# Shield.net
KiCad netlist of a schematic drawn in EAGLE
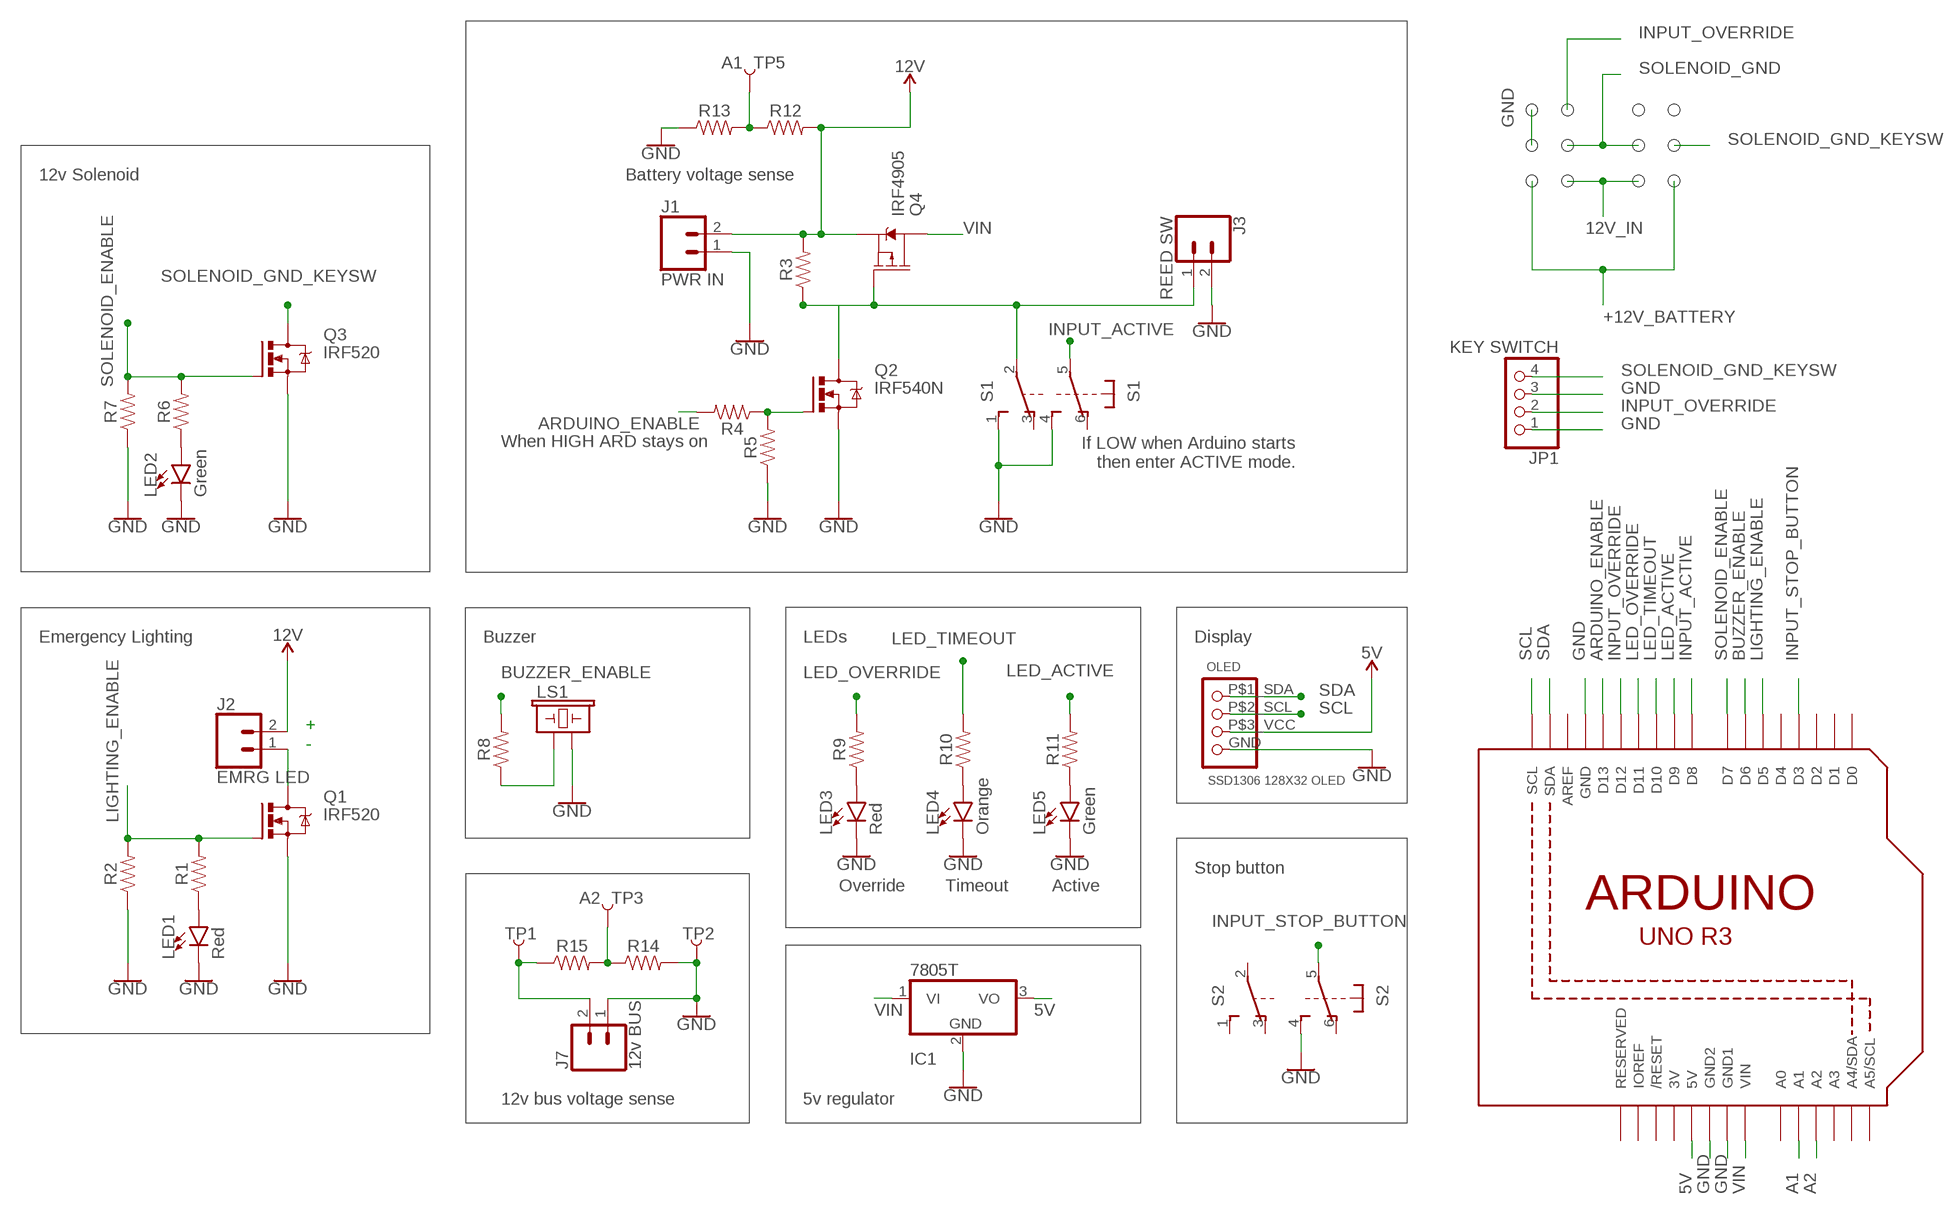
[diagram p0: schematic, sheet 1]

(export (version "E")
  (design (tool "Eeschema 10.0.6"))
  (components
    (comp (ref "IC1")
      (value "7805T")
      (footprint "eagle-import:TO220H")
      (libsource (lib "eagle-import") (part "78T05"))
    )
    (comp (ref "J1")
      (value "PWR IN")
      (footprint "eagle-import:SCREWTERMINAL-5MM-2")
      (libsource (lib "eagle-import") (part "CONN_025MM"))
    )
    (comp (ref "J2")
      (value "EMRG LED")
      (footprint "eagle-import:SCREWTERMINAL-5MM-2")
      (libsource (lib "eagle-import") (part "CONN_025MM"))
    )
    (comp (ref "J3")
      (value "REED SW")
      (footprint "eagle-import:SCREWTERMINAL-5MM-2")
      (libsource (lib "eagle-import") (part "CONN_025MM"))
    )
    (comp (ref "J7")
      (value "12v BUS")
      (footprint "eagle-import:SCREWTERMINAL-5MM-2")
      (libsource (lib "eagle-import") (part "CONN_025MM"))
    )
    (comp (ref "JP1")
      (value "KEY SWITCH")
      (footprint "eagle-import:1X04")
      (libsource (lib "eagle-import") (part "PINHD-1X4"))
    )
    (comp (ref "LED1")
      (value "Red")
      (footprint "eagle-import:LED_3MM")
      (libsource (lib "eagle-import") (part "LED3MM"))
    )
    (comp (ref "LED2")
      (value "Green")
      (footprint "eagle-import:LED_3MM")
      (libsource (lib "eagle-import") (part "LED3MM"))
    )
    (comp (ref "LED3")
      (value "Red")
      (footprint "eagle-import:LED_3MM")
      (libsource (lib "eagle-import") (part "LED3MM"))
    )
    (comp (ref "LED4")
      (value "Orange")
      (footprint "eagle-import:LED_3MM")
      (libsource (lib "eagle-import") (part "LED3MM"))
    )
    (comp (ref "LED5")
      (value "Green")
      (footprint "eagle-import:LED_3MM")
      (libsource (lib "eagle-import") (part "LED3MM"))
    )
    (comp (ref "LS1")
      (value "BUZZER")
      (footprint "eagle-import:BUZZER-12MM-KIT")
      (libsource (lib "eagle-import") (part "BUZZER-PTH_KIT"))
    )
    (comp (ref "OLED")
      (value "SSD1306 128X32 OLED")
      (footprint "eagle-import:SSD1306_128X32_OLED")
      (libsource (lib "eagle-import") (part "SSD1306_128X32_OLED"))
    )
    (comp (ref "Q1")
      (value "IRF520")
      (footprint "eagle-import:TO220BV")
      (libsource (lib "eagle-import") (part "IRF520"))
    )
    (comp (ref "Q2")
      (value "IRF540N")
      (footprint "eagle-import:TO220BV")
      (libsource (lib "eagle-import") (part "IRF540"))
    )
    (comp (ref "Q3")
      (value "IRF520")
      (footprint "eagle-import:TO220BV")
      (libsource (lib "eagle-import") (part "IRF520"))
    )
    (comp (ref "Q4")
      (value "IRF4905")
      (footprint "eagle-import:TO220V")
      (libsource (lib "eagle-import") (part "MOSFET_PCH-NDP6020P"))
    )
    (comp (ref "R1")
      (value "1k")
      (footprint "eagle-import:AXIAL-0.3")
      (libsource (lib "eagle-import") (part "1KOHM-HORIZ-1/4W-5%"))
    )
    (comp (ref "R2")
      (value "1k")
      (footprint "eagle-import:AXIAL-0.3")
      (libsource (lib "eagle-import") (part "1KOHM-HORIZ-1/4W-5%"))
    )
    (comp (ref "R3")
      (value "100k")
      (footprint "eagle-import:AXIAL-0.3")
      (libsource (lib "eagle-import") (part "1KOHM-HORIZ-1/4W-5%"))
    )
    (comp (ref "R4")
      (value "100")
      (footprint "eagle-import:AXIAL-0.3")
      (libsource (lib "eagle-import") (part "1KOHM-HORIZ-1/4W-5%"))
    )
    (comp (ref "R5")
      (value "10k")
      (footprint "eagle-import:AXIAL-0.3")
      (libsource (lib "eagle-import") (part "1KOHM-HORIZ-1/4W-5%"))
    )
    (comp (ref "R6")
      (value "1k")
      (footprint "eagle-import:AXIAL-0.3")
      (libsource (lib "eagle-import") (part "1KOHM-HORIZ-1/4W-5%"))
    )
    (comp (ref "R7")
      (value "1k")
      (footprint "eagle-import:AXIAL-0.3")
      (libsource (lib "eagle-import") (part "1KOHM-HORIZ-1/4W-5%"))
    )
    (comp (ref "R8")
      (value "100")
      (footprint "eagle-import:AXIAL-0.3")
      (libsource (lib "eagle-import") (part "1KOHM-HORIZ-1/4W-5%"))
    )
    (comp (ref "R9")
      (value "330")
      (footprint "eagle-import:AXIAL-0.3")
      (libsource (lib "eagle-import") (part "1KOHM-HORIZ-1/4W-5%"))
    )
    (comp (ref "R10")
      (value "330")
      (footprint "eagle-import:AXIAL-0.3")
      (libsource (lib "eagle-import") (part "1KOHM-HORIZ-1/4W-5%"))
    )
    (comp (ref "R11")
      (value "330")
      (footprint "eagle-import:AXIAL-0.3")
      (libsource (lib "eagle-import") (part "1KOHM-HORIZ-1/4W-5%"))
    )
    (comp (ref "R12")
      (value "1m")
      (footprint "eagle-import:AXIAL-0.3")
      (libsource (lib "eagle-import") (part "1KOHM-HORIZ-1/4W-5%"))
    )
    (comp (ref "R13")
      (value "100k")
      (footprint "eagle-import:AXIAL-0.3")
      (libsource (lib "eagle-import") (part "1KOHM-HORIZ-1/4W-5%"))
    )
    (comp (ref "R14")
      (value "100k")
      (footprint "eagle-import:AXIAL-0.3")
      (libsource (lib "eagle-import") (part "1KOHM-HORIZ-1/4W-5%"))
    )
    (comp (ref "R15")
      (value "1m")
      (footprint "eagle-import:AXIAL-0.3")
      (libsource (lib "eagle-import") (part "1KOHM-HORIZ-1/4W-5%"))
    )
    (comp (ref "S1")
      (value "8X8_PCB_PUSH_BUTTON_DPDT")
      (footprint "eagle-import:8X8_PCB_PUSH_BUTTON_DPDT")
      (libsource (lib "eagle-import") (part "8X8_PCB_PUSH_BUTTON_DPDT"))
    )
    (comp (ref "S2")
      (value "8X8_PCB_PUSH_BUTTON_DPDT")
      (footprint "eagle-import:8X8_PCB_PUSH_BUTTON_DPDT")
      (libsource (lib "eagle-import") (part "8X8_PCB_PUSH_BUTTON_DPDT"))
    )
    (comp (ref "TP1")
      (value "TEST-POINT3X5")
      (footprint "eagle-import:PAD.03X.05")
      (libsource (lib "eagle-import") (part "TEST-POINT3X5"))
    )
    (comp (ref "TP2")
      (value "TEST-POINT3X5")
      (footprint "eagle-import:PAD.03X.05")
      (libsource (lib "eagle-import") (part "TEST-POINT3X5"))
    )
    (comp (ref "TP3")
      (value "TEST-POINT3X5")
      (footprint "eagle-import:PAD.03X.05")
      (libsource (lib "eagle-import") (part "TEST-POINT3X5"))
    )
    (comp (ref "TP5")
      (value "TEST-POINT3X5")
      (footprint "eagle-import:PAD.03X.05")
      (libsource (lib "eagle-import") (part "TEST-POINT3X5"))
    )
    (comp (ref "U1")
      (value "ARDUINOR3-DIMENSION")
      (footprint "eagle-import:ARDUINOR3")
      (libsource (lib "eagle-import") (part "ARDUINOR3-DIMENSION"))
    )
  )
  (nets
    (net (code "2") (name "/3V") (class "Default")
      (node (ref "U1") (pin "3V") (pinfunction "3V_3V") (pintype "power_in"))
    )
    (net (code "4") (name "/A1") (class "Default")
      (node (ref "R12") (pin "P$1") (pinfunction "1_P$1") (pintype "passive"))
      (node (ref "R13") (pin "P$2") (pinfunction "2_P$2") (pintype "passive"))
      (node (ref "TP5") (pin "P$1") (pinfunction "1_P$1") (pintype "bidirectional"))
      (node (ref "U1") (pin "A1") (pinfunction "A1_A1") (pintype "bidirectional"))
    )
    (net (code "5") (name "/A2") (class "Default")
      (node (ref "R14") (pin "P$1") (pinfunction "1_P$1") (pintype "passive"))
      (node (ref "R15") (pin "P$2") (pinfunction "2_P$2") (pintype "passive"))
      (node (ref "TP3") (pin "P$1") (pinfunction "1_P$1") (pintype "bidirectional"))
      (node (ref "U1") (pin "A2") (pinfunction "A2_A2") (pintype "bidirectional"))
    )
    (net (code "6") (name "/ARDUINO_ENABLE") (class "Default")
      (node (ref "R4") (pin "P$2") (pinfunction "2_P$2") (pintype "passive"))
      (node (ref "U1") (pin "D13") (pinfunction "D13_D13") (pintype "bidirectional"))
    )
    (net (code "7") (name "/BUZZER_ENABLE") (class "Default")
      (node (ref "R8") (pin "P$2") (pinfunction "2_P$2") (pintype "passive"))
      (node (ref "U1") (pin "D6") (pinfunction "D6_D6") (pintype "bidirectional"))
    )
    (net (code "8") (name "/INPUT_ACTIVE") (class "Default")
      (node (ref "S1") (pin "5") (pinfunction "P_5") (pintype "passive"))
      (node (ref "U1") (pin "D8") (pinfunction "D8_D8") (pintype "bidirectional"))
    )
    (net (code "9") (name "/INPUT_OVERRIDE") (class "Default")
      (node (ref "JP1") (pin "2") (pinfunction "2_2") (pintype "passive"))
      (node (ref "U1") (pin "D12") (pinfunction "D12_D12") (pintype "bidirectional"))
    )
    (net (code "10") (name "/INPUT_STOP_BUTTON") (class "Default")
      (node (ref "S2") (pin "5") (pinfunction "P_5") (pintype "passive"))
      (node (ref "U1") (pin "D3") (pinfunction "D3_D3") (pintype "bidirectional"))
    )
    (net (code "11") (name "/LED_ACTIVE") (class "Default")
      (node (ref "R11") (pin "P$2") (pinfunction "2_P$2") (pintype "passive"))
      (node (ref "U1") (pin "D9") (pinfunction "D9_D9") (pintype "bidirectional"))
    )
    (net (code "12") (name "/LED_OVERRIDE") (class "Default")
      (node (ref "R9") (pin "P$2") (pinfunction "2_P$2") (pintype "passive"))
      (node (ref "U1") (pin "D11") (pinfunction "D11_D11") (pintype "bidirectional"))
    )
    (net (code "13") (name "/LED_TIMEOUT") (class "Default")
      (node (ref "R10") (pin "P$2") (pinfunction "2_P$2") (pintype "passive"))
      (node (ref "U1") (pin "D10") (pinfunction "D10_D10") (pintype "bidirectional"))
    )
    (net (code "14") (name "/LIGHTING_ENABLE") (class "Default")
      (node (ref "Q1") (pin "G") (pinfunction "G_G") (pintype "passive"))
      (node (ref "R1") (pin "P$2") (pinfunction "2_P$2") (pintype "passive"))
      (node (ref "R2") (pin "P$2") (pinfunction "2_P$2") (pintype "passive"))
      (node (ref "U1") (pin "D5") (pinfunction "D5_D5") (pintype "bidirectional"))
    )
    (net (code "15") (name "/SCL") (class "Default")
      (node (ref "OLED") (pin "P$2_SCL") (pinfunction "SCL_P$2_SCL") (pintype "passive"))
      (node (ref "U1") (pin "SCL") (pinfunction "SCL_SCL") (pintype "bidirectional"))
    )
    (net (code "16") (name "/SDA") (class "Default")
      (node (ref "OLED") (pin "P$1_SDA") (pinfunction "SDA_P$1_SDA") (pintype "passive"))
      (node (ref "U1") (pin "SDA") (pinfunction "SDA_SDA") (pintype "bidirectional"))
    )
    (net (code "17") (name "/SOLENOID_ENABLE") (class "Default")
      (node (ref "Q3") (pin "G") (pinfunction "G_G") (pintype "passive"))
      (node (ref "R6") (pin "P$2") (pinfunction "2_P$2") (pintype "passive"))
      (node (ref "R7") (pin "P$2") (pinfunction "2_P$2") (pintype "passive"))
      (node (ref "U1") (pin "D7") (pinfunction "D7_D7") (pintype "bidirectional"))
    )
    (net (code "19") (name "/SOLENOID_GND_KEYSW") (class "Default")
      (node (ref "JP1") (pin "4") (pinfunction "4_4") (pintype "passive"))
      (node (ref "Q3") (pin "D") (pinfunction "D_D") (pintype "passive"))
    )
    (net (code "20") (name "/VIN") (class "Default")
      (node (ref "IC1") (pin "1") (pinfunction "VI_1") (pintype "input"))
      (node (ref "Q4") (pin "2") (pinfunction "D_2") (pintype "bidirectional"))
      (node (ref "U1") (pin "VIN") (pinfunction "VIN_VIN") (pintype "power_in"))
    )
    (net (code "21") (name "5V") (class "Default")
      (node (ref "IC1") (pin "3") (pinfunction "VO_3") (pintype "passive"))
      (node (ref "OLED") (pin "P$3_VCC") (pinfunction "VCC_P$3_VCC") (pintype "passive"))
      (node (ref "U1") (pin "5V") (pinfunction "5V_5V") (pintype "power_in"))
    )
    (net (code "22") (name "12V") (class "Default")
      (node (ref "J1") (pin "2") (pinfunction "2_2") (pintype "passive"))
      (node (ref "J2") (pin "2") (pinfunction "2_2") (pintype "passive"))
      (node (ref "Q4") (pin "3") (pinfunction "S_3") (pintype "bidirectional"))
      (node (ref "R12") (pin "P$2") (pinfunction "2_P$2") (pintype "passive"))
      (node (ref "R3") (pin "P$2") (pinfunction "2_P$2") (pintype "passive"))
    )
    (net (code "23") (name "GND") (class "Default")
      (node (ref "IC1") (pin "2") (pinfunction "GND_2") (pintype "passive"))
      (node (ref "J1") (pin "1") (pinfunction "1_1") (pintype "passive"))
      (node (ref "J3") (pin "2") (pinfunction "2_2") (pintype "passive"))
      (node (ref "J7") (pin "1") (pinfunction "1_1") (pintype "passive"))
      (node (ref "JP1") (pin "1") (pinfunction "1_1") (pintype "passive"))
      (node (ref "JP1") (pin "3") (pinfunction "3_3") (pintype "passive"))
      (node (ref "LED1") (pin "K") (pinfunction "C_K") (pintype "passive"))
      (node (ref "LED2") (pin "K") (pinfunction "C_K") (pintype "passive"))
      (node (ref "LED3") (pin "K") (pinfunction "C_K") (pintype "passive"))
      (node (ref "LED4") (pin "K") (pinfunction "C_K") (pintype "passive"))
      (node (ref "LED5") (pin "K") (pinfunction "C_K") (pintype "passive"))
      (node (ref "LS1") (pin "-") (pinfunction "2_-") (pintype "passive"))
      (node (ref "OLED") (pin "GND") (pinfunction "GND_GND") (pintype "passive"))
      (node (ref "Q1") (pin "S") (pinfunction "S_S") (pintype "passive"))
      (node (ref "Q2") (pin "S") (pinfunction "S_S") (pintype "passive"))
      (node (ref "Q3") (pin "S") (pinfunction "S_S") (pintype "passive"))
      (node (ref "R13") (pin "P$1") (pinfunction "1_P$1") (pintype "passive"))
      (node (ref "R14") (pin "P$2") (pinfunction "2_P$2") (pintype "passive"))
      (node (ref "R2") (pin "P$1") (pinfunction "1_P$1") (pintype "passive"))
      (node (ref "R5") (pin "P$1") (pinfunction "1_P$1") (pintype "passive"))
      (node (ref "R7") (pin "P$1") (pinfunction "1_P$1") (pintype "passive"))
      (node (ref "S1") (pin "1") (pinfunction "S_1") (pintype "passive"))
      (node (ref "S1") (pin "4") (pinfunction "S_4") (pintype "passive"))
      (node (ref "S2") (pin "4") (pinfunction "S_4") (pintype "passive"))
      (node (ref "TP2") (pin "P$1") (pinfunction "1_P$1") (pintype "bidirectional"))
      (node (ref "U1") (pin "GND") (pinfunction "GND_GND") (pintype "power_in"))
      (node (ref "U1") (pin "GND1") (pinfunction "GND1_GND1") (pintype "power_in"))
      (node (ref "U1") (pin "GND2") (pinfunction "GND2_GND2") (pintype "power_in"))
    )
    (net (code "24") (name "Net-(J2-Pad1)") (class "Default")
      (node (ref "J2") (pin "1") (pinfunction "1_1") (pintype "passive"))
      (node (ref "Q1") (pin "D") (pinfunction "D_D") (pintype "passive"))
    )
    (net (code "25") (name "Net-(LS1-1)") (class "Default")
      (node (ref "LS1") (pin "+") (pinfunction "1_+") (pintype "passive"))
      (node (ref "R8") (pin "P$1") (pinfunction "1_P$1") (pintype "passive"))
    )
    (net (code "26") (name "Net-(Q4-G)") (class "Default")
      (node (ref "J3") (pin "1") (pinfunction "1_1") (pintype "passive"))
      (node (ref "Q2") (pin "D") (pinfunction "D_D") (pintype "passive"))
      (node (ref "Q4") (pin "1") (pinfunction "G_1") (pintype "bidirectional"))
      (node (ref "R3") (pin "P$1") (pinfunction "1_P$1") (pintype "passive"))
      (node (ref "S1") (pin "2") (pinfunction "P_2") (pintype "passive"))
    )
    (net (code "27") (name "Net-(R1-1)") (class "Default")
      (node (ref "LED1") (pin "A") (pinfunction "A_A") (pintype "passive"))
      (node (ref "R1") (pin "P$1") (pinfunction "1_P$1") (pintype "passive"))
    )
    (net (code "28") (name "Net-(R4-1)") (class "Default")
      (node (ref "Q2") (pin "G") (pinfunction "G_G") (pintype "passive"))
      (node (ref "R4") (pin "P$1") (pinfunction "1_P$1") (pintype "passive"))
      (node (ref "R5") (pin "P$2") (pinfunction "2_P$2") (pintype "passive"))
    )
    (net (code "29") (name "Net-(R6-1)") (class "Default")
      (node (ref "LED2") (pin "A") (pinfunction "A_A") (pintype "passive"))
      (node (ref "R6") (pin "P$1") (pinfunction "1_P$1") (pintype "passive"))
    )
    (net (code "30") (name "Net-(R9-1)") (class "Default")
      (node (ref "LED3") (pin "A") (pinfunction "A_A") (pintype "passive"))
      (node (ref "R9") (pin "P$1") (pinfunction "1_P$1") (pintype "passive"))
    )
    (net (code "31") (name "Net-(R10-1)") (class "Default")
      (node (ref "LED4") (pin "A") (pinfunction "A_A") (pintype "passive"))
      (node (ref "R10") (pin "P$1") (pinfunction "1_P$1") (pintype "passive"))
    )
    (net (code "32") (name "Net-(R11-1)") (class "Default")
      (node (ref "LED5") (pin "A") (pinfunction "A_A") (pintype "passive"))
      (node (ref "R11") (pin "P$1") (pinfunction "1_P$1") (pintype "passive"))
    )
    (net (code "33") (name "Net-(R15-1)") (class "Default")
      (node (ref "J7") (pin "2") (pinfunction "2_2") (pintype "passive"))
      (node (ref "R15") (pin "P$1") (pinfunction "1_P$1") (pintype "passive"))
      (node (ref "TP1") (pin "P$1") (pinfunction "1_P$1") (pintype "bidirectional"))
    )
    (net (code "34") (name "unconnected-(S1A-O-Pad6)") (class "Default")
      (node (ref "S1") (pin "6") (pinfunction "O_6") (pintype "passive"))
    )
    (net (code "35") (name "unconnected-(S1B-O-Pad3)") (class "Default")
      (node (ref "S1") (pin "3") (pinfunction "O_3") (pintype "passive"))
    )
    (net (code "36") (name "unconnected-(S2A-O-Pad6)") (class "Default")
      (node (ref "S2") (pin "6") (pinfunction "O_6") (pintype "passive"))
    )
    (net (code "37") (name "unconnected-(S2B-O-Pad3)") (class "Default")
      (node (ref "S2") (pin "3") (pinfunction "O_3") (pintype "passive"))
    )
    (net (code "38") (name "unconnected-(S2B-P-Pad2)") (class "Default")
      (node (ref "S2") (pin "2") (pinfunction "P_2") (pintype "passive"))
    )
    (net (code "39") (name "unconnected-(S2B-S-Pad1)") (class "Default")
      (node (ref "S2") (pin "1") (pinfunction "S_1") (pintype "passive"))
    )
    (net (code "40") (name "unconnected-(U1-A4{slash}SDA-PadA4)") (class "Default")
      (node (ref "U1") (pin "A4") (pinfunction "A4/SDA_A4") (pintype "bidirectional"))
    )
    (net (code "41") (name "unconnected-(U1-A5{slash}SCL-PadA5)") (class "Default")
      (node (ref "U1") (pin "A5") (pinfunction "A5/SCL_A5") (pintype "bidirectional"))
    )
    (net (code "42") (name "unconnected-(U1-PadA0)") (class "Default")
      (node (ref "U1") (pin "A0") (pinfunction "A0_A0") (pintype "bidirectional"))
    )
    (net (code "43") (name "unconnected-(U1-PadA3)") (class "Default")
      (node (ref "U1") (pin "A3") (pinfunction "A3_A3") (pintype "bidirectional"))
    )
    (net (code "44") (name "unconnected-(U1-PadAREF)") (class "Default")
      (node (ref "U1") (pin "AREF") (pinfunction "AREF_AREF") (pintype "bidirectional"))
    )
    (net (code "45") (name "unconnected-(U1-PadD0)") (class "Default")
      (node (ref "U1") (pin "D0") (pinfunction "D0_D0") (pintype "bidirectional"))
    )
    (net (code "46") (name "unconnected-(U1-PadD1)") (class "Default")
      (node (ref "U1") (pin "D1") (pinfunction "D1_D1") (pintype "bidirectional"))
    )
    (net (code "47") (name "unconnected-(U1-PadD2)") (class "Default")
      (node (ref "U1") (pin "D2") (pinfunction "D2_D2") (pintype "bidirectional"))
    )
    (net (code "48") (name "unconnected-(U1-PadD4)") (class "Default")
      (node (ref "U1") (pin "D4") (pinfunction "D4_D4") (pintype "bidirectional"))
    )
    (net (code "49") (name "unconnected-(U1-PadIOREF)") (class "Default")
      (node (ref "U1") (pin "IOREF") (pinfunction "IOREF_IOREF") (pintype "output"))
    )
    (net (code "50") (name "unconnected-(U1-PadRESERVED)") (class "Default")
      (node (ref "U1") (pin "RESERVED") (pinfunction "RESERVED_RESERVED") (pintype "no_connect"))
    )
    (net (code "51") (name "unconnected-(U1-{slash}RESET-PadRESET)") (class "Default")
      (node (ref "U1") (pin "RESET") (pinfunction "/RESET_RESET") (pintype "bidirectional"))
    )
  )
)
